# FINAL_schematic.net
KiCad netlist of a schematic drawn in EAGLE
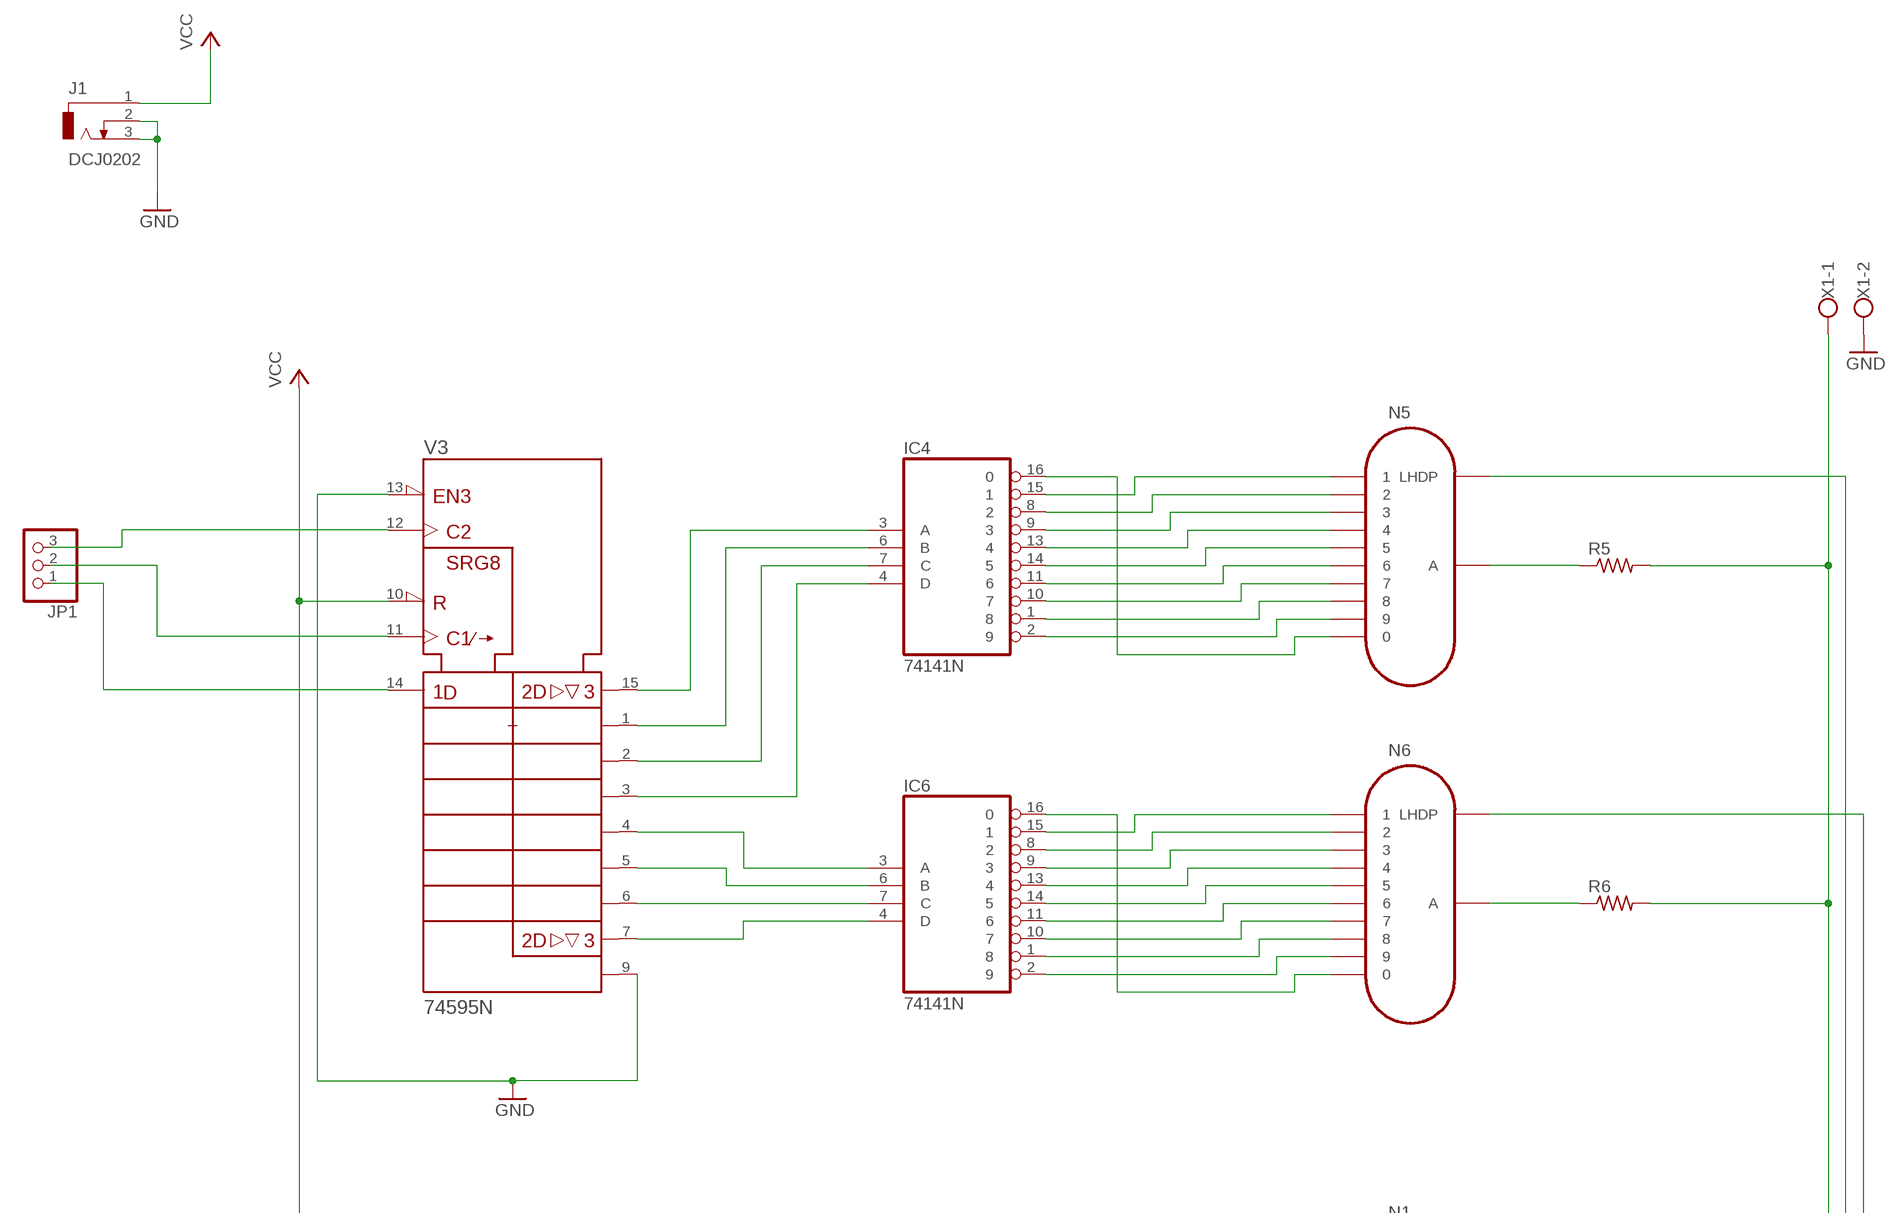
[diagram p0: schematic, sheet 1, part 1 of 2]
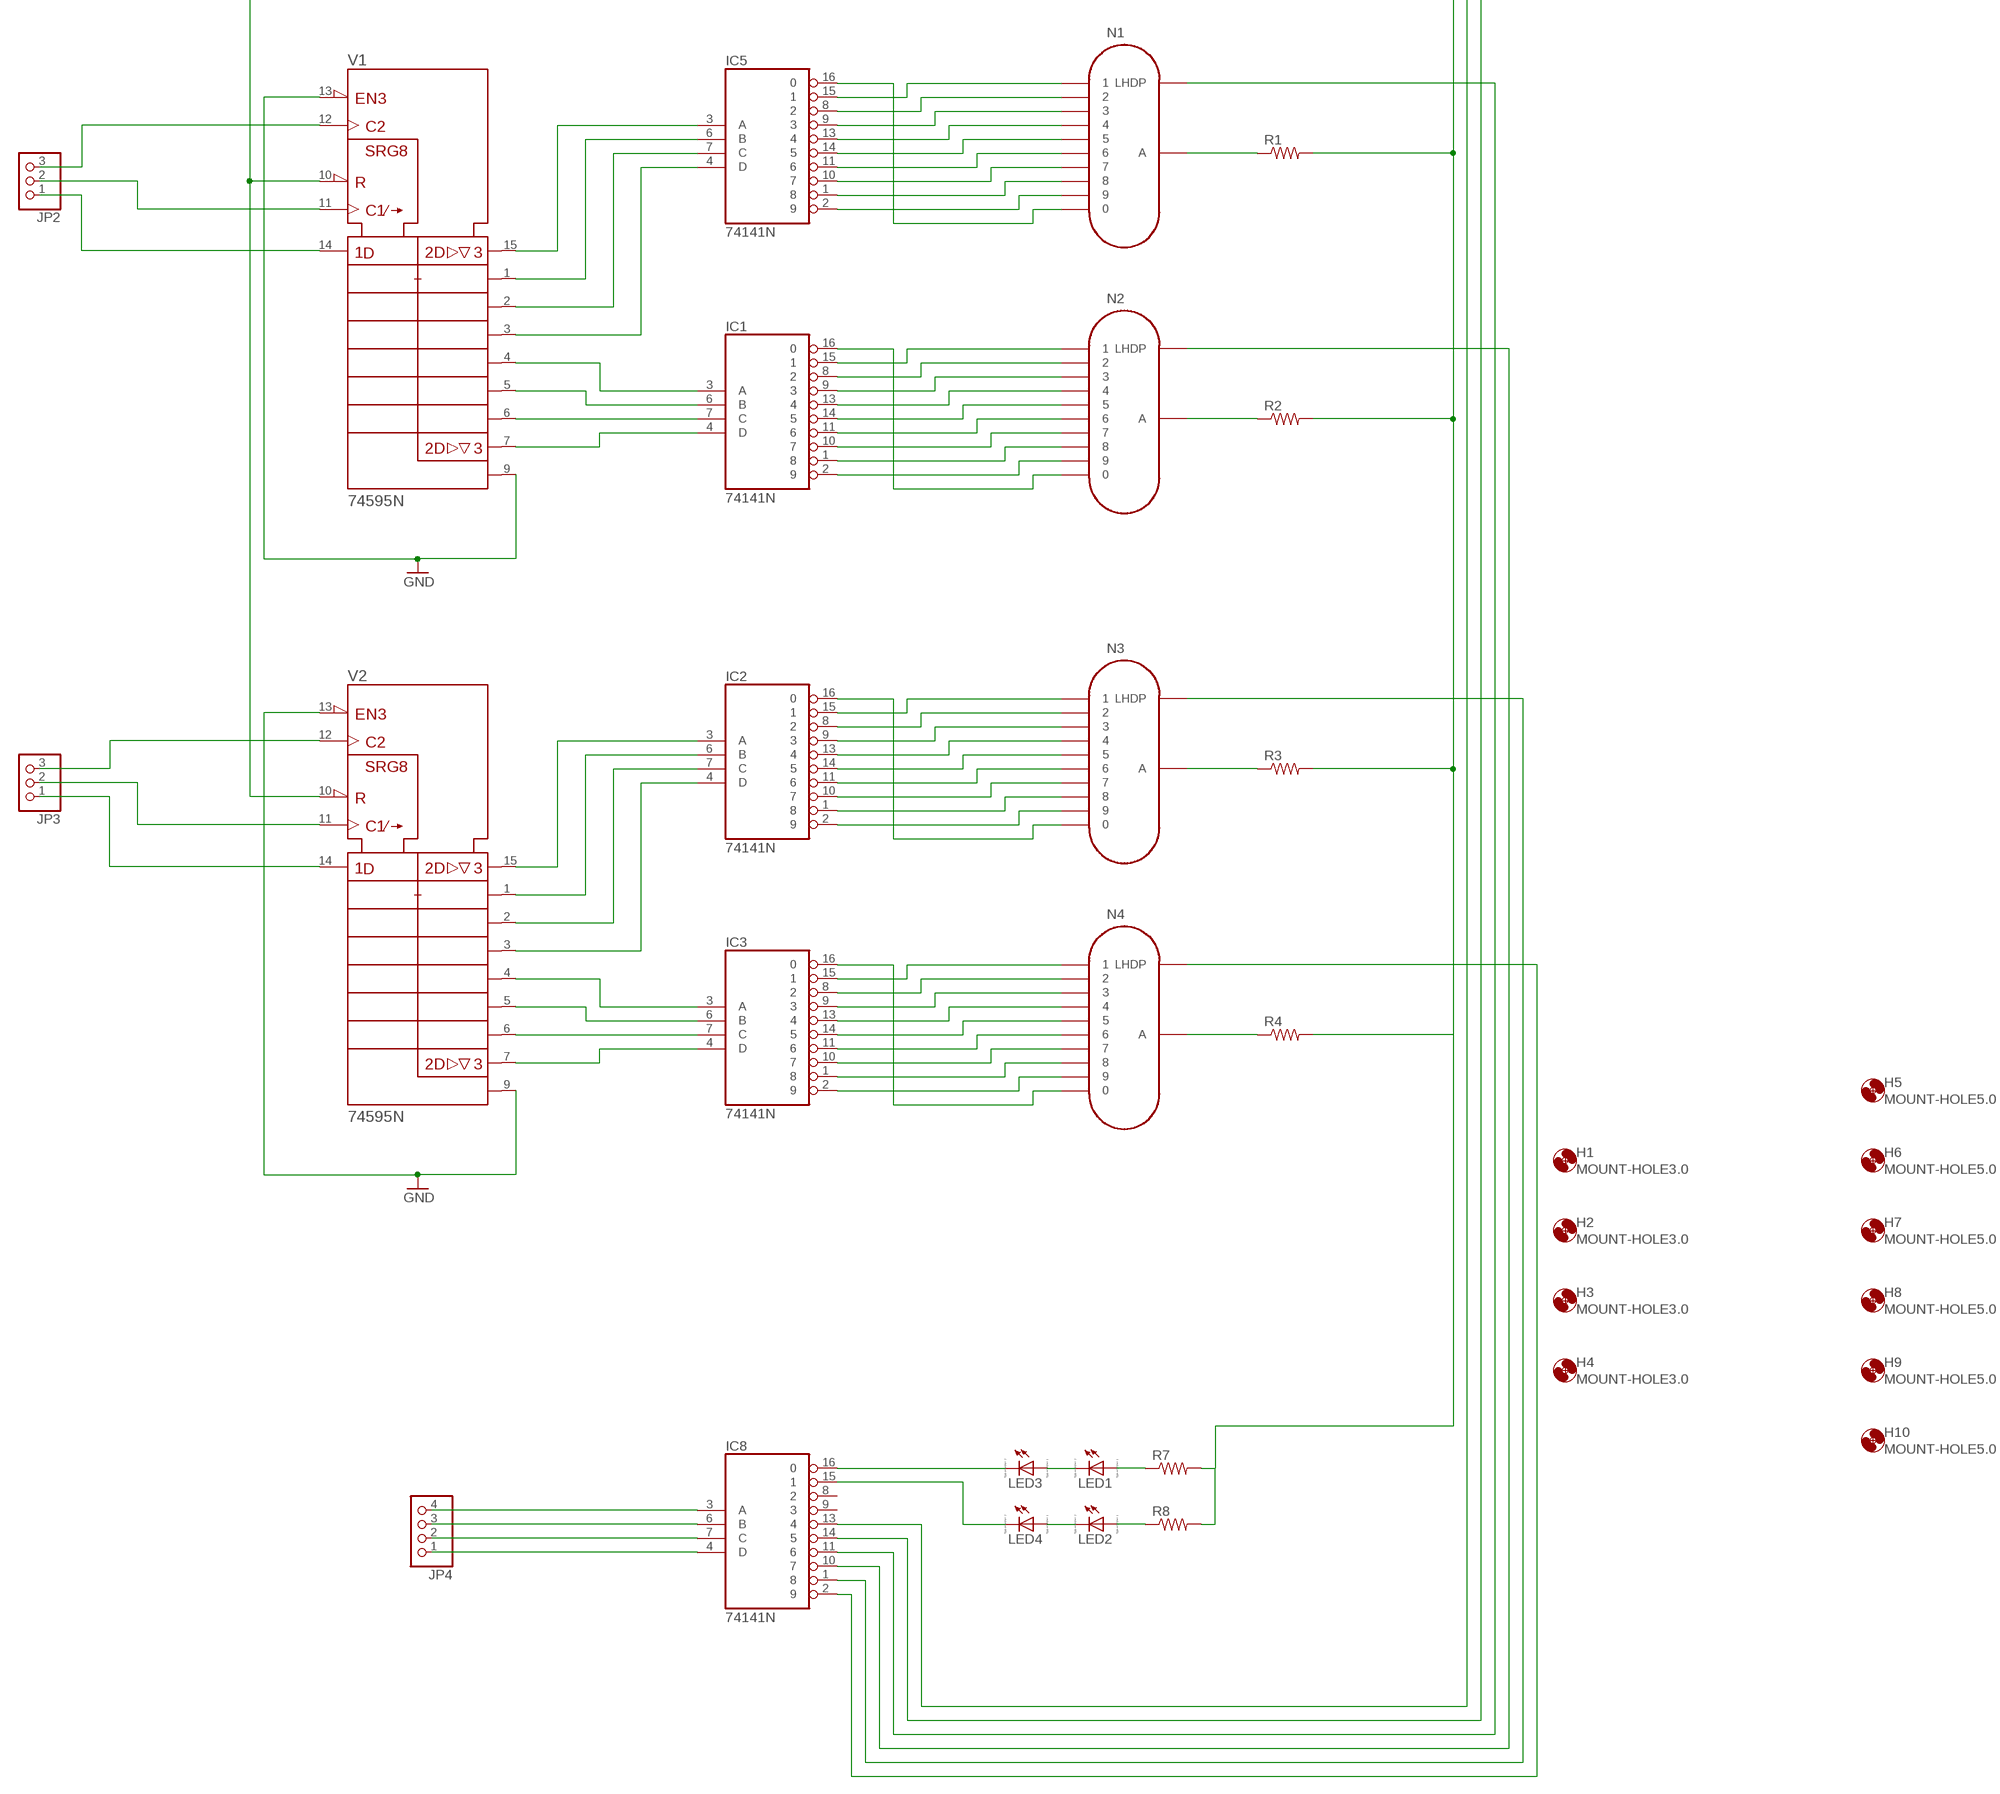
[diagram p1: schematic, sheet 1, part 2 of 2]

(export (version "E")
  (design (tool "Eeschema 10.0.6"))
  (components
    (comp (ref "H1")
      (value "MOUNT-HOLE3.0")
      (footprint "eagle-import:3,0")
      (libsource (lib "eagle-import") (part "MOUNT-HOLE3.0"))
    )
    (comp (ref "H2")
      (value "MOUNT-HOLE3.0")
      (footprint "eagle-import:3,0")
      (libsource (lib "eagle-import") (part "MOUNT-HOLE3.0"))
    )
    (comp (ref "H3")
      (value "MOUNT-HOLE3.0")
      (footprint "eagle-import:3,0")
      (libsource (lib "eagle-import") (part "MOUNT-HOLE3.0"))
    )
    (comp (ref "H4")
      (value "MOUNT-HOLE3.0")
      (footprint "eagle-import:3,0")
      (libsource (lib "eagle-import") (part "MOUNT-HOLE3.0"))
    )
    (comp (ref "H5")
      (value "MOUNT-HOLE5.0")
      (footprint "eagle-import:5,0")
      (libsource (lib "eagle-import") (part "MOUNT-HOLE5.0"))
    )
    (comp (ref "H6")
      (value "MOUNT-HOLE5.0")
      (footprint "eagle-import:5,0")
      (libsource (lib "eagle-import") (part "MOUNT-HOLE5.0"))
    )
    (comp (ref "H7")
      (value "MOUNT-HOLE5.0")
      (footprint "eagle-import:5,0")
      (libsource (lib "eagle-import") (part "MOUNT-HOLE5.0"))
    )
    (comp (ref "H8")
      (value "MOUNT-HOLE5.0")
      (footprint "eagle-import:5,0")
      (libsource (lib "eagle-import") (part "MOUNT-HOLE5.0"))
    )
    (comp (ref "H9")
      (value "MOUNT-HOLE5.0")
      (footprint "eagle-import:5,0")
      (libsource (lib "eagle-import") (part "MOUNT-HOLE5.0"))
    )
    (comp (ref "H10")
      (value "MOUNT-HOLE5.0")
      (footprint "eagle-import:5,0")
      (libsource (lib "eagle-import") (part "MOUNT-HOLE5.0"))
    )
    (comp (ref "IC1")
      (value "74141N")
      (footprint "eagle-import:DIL16")
      (libsource (lib "eagle-import") (part "74141N"))
    )
    (comp (ref "IC2")
      (value "74141N")
      (footprint "eagle-import:DIL16")
      (libsource (lib "eagle-import") (part "74141N"))
    )
    (comp (ref "IC3")
      (value "74141N")
      (footprint "eagle-import:DIL16")
      (libsource (lib "eagle-import") (part "74141N"))
    )
    (comp (ref "IC4")
      (value "74141N")
      (footprint "eagle-import:DIL16")
      (libsource (lib "eagle-import") (part "74141N"))
    )
    (comp (ref "IC5")
      (value "74141N")
      (footprint "eagle-import:DIL16")
      (libsource (lib "eagle-import") (part "74141N"))
    )
    (comp (ref "IC6")
      (value "74141N")
      (footprint "eagle-import:DIL16")
      (libsource (lib "eagle-import") (part "74141N"))
    )
    (comp (ref "IC8")
      (value "74141N")
      (footprint "eagle-import:DIL16")
      (libsource (lib "eagle-import") (part "74141N"))
    )
    (comp (ref "J1")
      (value "DCJ0202")
      (footprint "eagle-import:DCJ0202")
      (libsource (lib "eagle-import") (part "DCJ0202"))
    )
    (comp (ref "JP1")
      (value "PINHD-1X3")
      (footprint "eagle-import:1X03")
      (libsource (lib "eagle-import") (part "PINHD-1X3"))
    )
    (comp (ref "JP2")
      (value "PINHD-1X3")
      (footprint "eagle-import:1X03")
      (libsource (lib "eagle-import") (part "PINHD-1X3"))
    )
    (comp (ref "JP3")
      (value "PINHD-1X3")
      (footprint "eagle-import:1X03")
      (libsource (lib "eagle-import") (part "PINHD-1X3"))
    )
    (comp (ref "JP4")
      (value "PINHD-1X4")
      (footprint "eagle-import:1X04")
      (libsource (lib "eagle-import") (part "PINHD-1X4"))
    )
    (comp (ref "LED1")
      (value "LED_ELD260")
      (footprint "eagle-import:LED_LD260")
      (libsource (lib "eagle-import") (part "LED_ELD260"))
    )
    (comp (ref "LED2")
      (value "LED_ELD260")
      (footprint "eagle-import:LED_LD260")
      (libsource (lib "eagle-import") (part "LED_ELD260"))
    )
    (comp (ref "LED3")
      (value "LED_ELD260")
      (footprint "eagle-import:LED_LD260")
      (libsource (lib "eagle-import") (part "LED_ELD260"))
    )
    (comp (ref "LED4")
      (value "LED_ELD260")
      (footprint "eagle-import:LED_LD260")
      (libsource (lib "eagle-import") (part "LED_ELD260"))
    )
    (comp (ref "N1")
      (value "IN-12B")
      (footprint "eagle-import:IN-12")
      (libsource (lib "eagle-import") (part "IN-12B"))
    )
    (comp (ref "N2")
      (value "IN-12B")
      (footprint "eagle-import:IN-12")
      (libsource (lib "eagle-import") (part "IN-12B"))
    )
    (comp (ref "N3")
      (value "IN-12B")
      (footprint "eagle-import:IN-12")
      (libsource (lib "eagle-import") (part "IN-12B"))
    )
    (comp (ref "N4")
      (value "IN-12B")
      (footprint "eagle-import:IN-12")
      (libsource (lib "eagle-import") (part "IN-12B"))
    )
    (comp (ref "N5")
      (value "IN-12B")
      (footprint "eagle-import:IN-12")
      (libsource (lib "eagle-import") (part "IN-12B"))
    )
    (comp (ref "N6")
      (value "IN-12B")
      (footprint "eagle-import:IN-12")
      (libsource (lib "eagle-import") (part "IN-12B"))
    )
    (comp (ref "R1")
      (value "R-US_0207/10")
      (footprint "eagle-import:0207_10")
      (libsource (lib "eagle-import") (part "R-US_0207/10"))
    )
    (comp (ref "R2")
      (value "R-US_0207/10")
      (footprint "eagle-import:0207_10")
      (libsource (lib "eagle-import") (part "R-US_0207/10"))
    )
    (comp (ref "R3")
      (value "R-US_0207/10")
      (footprint "eagle-import:0207_10")
      (libsource (lib "eagle-import") (part "R-US_0207/10"))
    )
    (comp (ref "R4")
      (value "R-US_0207/10")
      (footprint "eagle-import:0207_10")
      (libsource (lib "eagle-import") (part "R-US_0207/10"))
    )
    (comp (ref "R5")
      (value "R-US_0207/10")
      (footprint "eagle-import:0207_10")
      (libsource (lib "eagle-import") (part "R-US_0207/10"))
    )
    (comp (ref "R6")
      (value "R-US_0207/10")
      (footprint "eagle-import:0207_10")
      (libsource (lib "eagle-import") (part "R-US_0207/10"))
    )
    (comp (ref "R7")
      (value "R-US_0207/10")
      (footprint "eagle-import:0207_10")
      (libsource (lib "eagle-import") (part "R-US_0207/10"))
    )
    (comp (ref "R8")
      (value "R-US_0207/10")
      (footprint "eagle-import:0207_10")
      (libsource (lib "eagle-import") (part "R-US_0207/10"))
    )
    (comp (ref "V1")
      (value "74595N")
      (footprint "eagle-import:DIL16")
      (libsource (lib "eagle-import") (part "74595N"))
    )
    (comp (ref "V2")
      (value "74595N")
      (footprint "eagle-import:DIL16")
      (libsource (lib "eagle-import") (part "74595N"))
    )
    (comp (ref "V3")
      (value "74595N")
      (footprint "eagle-import:DIL16")
      (libsource (lib "eagle-import") (part "74595N"))
    )
    (comp (ref "X1")
      (value "W237-102")
      (footprint "eagle-import:W237-102")
      (fields (field (name "MPN") "237-102"))
      (libsource (lib "eagle-import") (part "W237-102"))
    )
  )
  (nets
    (net (code "1") (name "GND") (class "Default")
      (node (ref "J1") (pin "2") (pinfunction "2_2") (pintype "passive"))
      (node (ref "J1") (pin "3") (pinfunction "3_3") (pintype "passive"))
      (node (ref "V1") (pin "13") (pinfunction "~{G}_13") (pintype "input"))
      (node (ref "V1") (pin "9") (pinfunction "QH*_9") (pintype "output"))
      (node (ref "V2") (pin "13") (pinfunction "~{G}_13") (pintype "input"))
      (node (ref "V2") (pin "9") (pinfunction "QH*_9") (pintype "output"))
      (node (ref "V3") (pin "13") (pinfunction "~{G}_13") (pintype "input"))
      (node (ref "V3") (pin "9") (pinfunction "QH*_9") (pintype "output"))
      (node (ref "X1") (pin "2") (pinfunction "KL_2") (pintype "passive"))
    )
    (net (code "2") (name "Net-(IC1A-0)") (class "Default")
      (node (ref "IC1") (pin "16") (pinfunction "0_16") (pintype "open_collector"))
      (node (ref "N2") (pin "0") (pinfunction "0_0") (pintype "bidirectional"))
    )
    (net (code "3") (name "Net-(IC1A-1)") (class "Default")
      (node (ref "IC1") (pin "15") (pinfunction "1_15") (pintype "open_collector"))
      (node (ref "N2") (pin "1") (pinfunction "1_1") (pintype "bidirectional"))
    )
    (net (code "4") (name "Net-(IC1A-2)") (class "Default")
      (node (ref "IC1") (pin "8") (pinfunction "2_8") (pintype "open_collector"))
      (node (ref "N2") (pin "2") (pinfunction "2_2") (pintype "bidirectional"))
    )
    (net (code "5") (name "Net-(IC1A-3)") (class "Default")
      (node (ref "IC1") (pin "9") (pinfunction "3_9") (pintype "open_collector"))
      (node (ref "N2") (pin "3") (pinfunction "3_3") (pintype "bidirectional"))
    )
    (net (code "6") (name "Net-(IC1A-4)") (class "Default")
      (node (ref "IC1") (pin "13") (pinfunction "4_13") (pintype "open_collector"))
      (node (ref "N2") (pin "4") (pinfunction "4_4") (pintype "bidirectional"))
    )
    (net (code "7") (name "Net-(IC1A-5)") (class "Default")
      (node (ref "IC1") (pin "14") (pinfunction "5_14") (pintype "open_collector"))
      (node (ref "N2") (pin "5") (pinfunction "5_5") (pintype "bidirectional"))
    )
    (net (code "8") (name "Net-(IC1A-6)") (class "Default")
      (node (ref "IC1") (pin "11") (pinfunction "6_11") (pintype "open_collector"))
      (node (ref "N2") (pin "6") (pinfunction "6_6") (pintype "bidirectional"))
    )
    (net (code "9") (name "Net-(IC1A-7)") (class "Default")
      (node (ref "IC1") (pin "10") (pinfunction "7_10") (pintype "open_collector"))
      (node (ref "N2") (pin "7") (pinfunction "7_7") (pintype "bidirectional"))
    )
    (net (code "10") (name "Net-(IC1A-8)") (class "Default")
      (node (ref "IC1") (pin "1") (pinfunction "8_1") (pintype "open_collector"))
      (node (ref "N2") (pin "8") (pinfunction "8_8") (pintype "bidirectional"))
    )
    (net (code "11") (name "Net-(IC1A-9)") (class "Default")
      (node (ref "IC1") (pin "2") (pinfunction "9_2") (pintype "open_collector"))
      (node (ref "N2") (pin "9") (pinfunction "9_9") (pintype "bidirectional"))
    )
    (net (code "12") (name "Net-(IC1A-A)") (class "Default")
      (node (ref "IC1") (pin "3") (pinfunction "A_3") (pintype "input"))
      (node (ref "V1") (pin "4") (pinfunction "QE_4") (pintype "tri_state"))
    )
    (net (code "13") (name "Net-(IC1A-B)") (class "Default")
      (node (ref "IC1") (pin "6") (pinfunction "B_6") (pintype "input"))
      (node (ref "V1") (pin "5") (pinfunction "QF_5") (pintype "tri_state"))
    )
    (net (code "14") (name "Net-(IC1A-C)") (class "Default")
      (node (ref "IC1") (pin "7") (pinfunction "C_7") (pintype "input"))
      (node (ref "V1") (pin "6") (pinfunction "QG_6") (pintype "tri_state"))
    )
    (net (code "15") (name "Net-(IC1A-D)") (class "Default")
      (node (ref "IC1") (pin "4") (pinfunction "D_4") (pintype "input"))
      (node (ref "V1") (pin "7") (pinfunction "QH_7") (pintype "tri_state"))
    )
    (net (code "16") (name "Net-(IC2A-0)") (class "Default")
      (node (ref "IC2") (pin "16") (pinfunction "0_16") (pintype "open_collector"))
      (node (ref "N3") (pin "0") (pinfunction "0_0") (pintype "bidirectional"))
    )
    (net (code "17") (name "Net-(IC2A-1)") (class "Default")
      (node (ref "IC2") (pin "15") (pinfunction "1_15") (pintype "open_collector"))
      (node (ref "N3") (pin "1") (pinfunction "1_1") (pintype "bidirectional"))
    )
    (net (code "18") (name "Net-(IC2A-2)") (class "Default")
      (node (ref "IC2") (pin "8") (pinfunction "2_8") (pintype "open_collector"))
      (node (ref "N3") (pin "2") (pinfunction "2_2") (pintype "bidirectional"))
    )
    (net (code "19") (name "Net-(IC2A-3)") (class "Default")
      (node (ref "IC2") (pin "9") (pinfunction "3_9") (pintype "open_collector"))
      (node (ref "N3") (pin "3") (pinfunction "3_3") (pintype "bidirectional"))
    )
    (net (code "20") (name "Net-(IC2A-4)") (class "Default")
      (node (ref "IC2") (pin "13") (pinfunction "4_13") (pintype "open_collector"))
      (node (ref "N3") (pin "4") (pinfunction "4_4") (pintype "bidirectional"))
    )
    (net (code "21") (name "Net-(IC2A-5)") (class "Default")
      (node (ref "IC2") (pin "14") (pinfunction "5_14") (pintype "open_collector"))
      (node (ref "N3") (pin "5") (pinfunction "5_5") (pintype "bidirectional"))
    )
    (net (code "22") (name "Net-(IC2A-6)") (class "Default")
      (node (ref "IC2") (pin "11") (pinfunction "6_11") (pintype "open_collector"))
      (node (ref "N3") (pin "6") (pinfunction "6_6") (pintype "bidirectional"))
    )
    (net (code "23") (name "Net-(IC2A-7)") (class "Default")
      (node (ref "IC2") (pin "10") (pinfunction "7_10") (pintype "open_collector"))
      (node (ref "N3") (pin "7") (pinfunction "7_7") (pintype "bidirectional"))
    )
    (net (code "24") (name "Net-(IC2A-8)") (class "Default")
      (node (ref "IC2") (pin "1") (pinfunction "8_1") (pintype "open_collector"))
      (node (ref "N3") (pin "8") (pinfunction "8_8") (pintype "bidirectional"))
    )
    (net (code "25") (name "Net-(IC2A-9)") (class "Default")
      (node (ref "IC2") (pin "2") (pinfunction "9_2") (pintype "open_collector"))
      (node (ref "N3") (pin "9") (pinfunction "9_9") (pintype "bidirectional"))
    )
    (net (code "26") (name "Net-(IC2A-A)") (class "Default")
      (node (ref "IC2") (pin "3") (pinfunction "A_3") (pintype "input"))
      (node (ref "V2") (pin "15") (pinfunction "QA_15") (pintype "tri_state"))
    )
    (net (code "27") (name "Net-(IC2A-B)") (class "Default")
      (node (ref "IC2") (pin "6") (pinfunction "B_6") (pintype "input"))
      (node (ref "V2") (pin "1") (pinfunction "QB_1") (pintype "tri_state"))
    )
    (net (code "28") (name "Net-(IC2A-C)") (class "Default")
      (node (ref "IC2") (pin "7") (pinfunction "C_7") (pintype "input"))
      (node (ref "V2") (pin "2") (pinfunction "QC_2") (pintype "tri_state"))
    )
    (net (code "29") (name "Net-(IC2A-D)") (class "Default")
      (node (ref "IC2") (pin "4") (pinfunction "D_4") (pintype "input"))
      (node (ref "V2") (pin "3") (pinfunction "QD_3") (pintype "tri_state"))
    )
    (net (code "30") (name "Net-(IC3A-0)") (class "Default")
      (node (ref "IC3") (pin "16") (pinfunction "0_16") (pintype "open_collector"))
      (node (ref "N4") (pin "0") (pinfunction "0_0") (pintype "bidirectional"))
    )
    (net (code "31") (name "Net-(IC3A-1)") (class "Default")
      (node (ref "IC3") (pin "15") (pinfunction "1_15") (pintype "open_collector"))
      (node (ref "N4") (pin "1") (pinfunction "1_1") (pintype "bidirectional"))
    )
    (net (code "32") (name "Net-(IC3A-2)") (class "Default")
      (node (ref "IC3") (pin "8") (pinfunction "2_8") (pintype "open_collector"))
      (node (ref "N4") (pin "2") (pinfunction "2_2") (pintype "bidirectional"))
    )
    (net (code "33") (name "Net-(IC3A-3)") (class "Default")
      (node (ref "IC3") (pin "9") (pinfunction "3_9") (pintype "open_collector"))
      (node (ref "N4") (pin "3") (pinfunction "3_3") (pintype "bidirectional"))
    )
    (net (code "34") (name "Net-(IC3A-4)") (class "Default")
      (node (ref "IC3") (pin "13") (pinfunction "4_13") (pintype "open_collector"))
      (node (ref "N4") (pin "4") (pinfunction "4_4") (pintype "bidirectional"))
    )
    (net (code "35") (name "Net-(IC3A-5)") (class "Default")
      (node (ref "IC3") (pin "14") (pinfunction "5_14") (pintype "open_collector"))
      (node (ref "N4") (pin "5") (pinfunction "5_5") (pintype "bidirectional"))
    )
    (net (code "36") (name "Net-(IC3A-6)") (class "Default")
      (node (ref "IC3") (pin "11") (pinfunction "6_11") (pintype "open_collector"))
      (node (ref "N4") (pin "6") (pinfunction "6_6") (pintype "bidirectional"))
    )
    (net (code "37") (name "Net-(IC3A-7)") (class "Default")
      (node (ref "IC3") (pin "10") (pinfunction "7_10") (pintype "open_collector"))
      (node (ref "N4") (pin "7") (pinfunction "7_7") (pintype "bidirectional"))
    )
    (net (code "38") (name "Net-(IC3A-8)") (class "Default")
      (node (ref "IC3") (pin "1") (pinfunction "8_1") (pintype "open_collector"))
      (node (ref "N4") (pin "8") (pinfunction "8_8") (pintype "bidirectional"))
    )
    (net (code "39") (name "Net-(IC3A-9)") (class "Default")
      (node (ref "IC3") (pin "2") (pinfunction "9_2") (pintype "open_collector"))
      (node (ref "N4") (pin "9") (pinfunction "9_9") (pintype "bidirectional"))
    )
    (net (code "40") (name "Net-(IC3A-A)") (class "Default")
      (node (ref "IC3") (pin "3") (pinfunction "A_3") (pintype "input"))
      (node (ref "V2") (pin "4") (pinfunction "QE_4") (pintype "tri_state"))
    )
    (net (code "41") (name "Net-(IC3A-B)") (class "Default")
      (node (ref "IC3") (pin "6") (pinfunction "B_6") (pintype "input"))
      (node (ref "V2") (pin "5") (pinfunction "QF_5") (pintype "tri_state"))
    )
    (net (code "42") (name "Net-(IC3A-C)") (class "Default")
      (node (ref "IC3") (pin "7") (pinfunction "C_7") (pintype "input"))
      (node (ref "V2") (pin "6") (pinfunction "QG_6") (pintype "tri_state"))
    )
    (net (code "43") (name "Net-(IC3A-D)") (class "Default")
      (node (ref "IC3") (pin "4") (pinfunction "D_4") (pintype "input"))
      (node (ref "V2") (pin "7") (pinfunction "QH_7") (pintype "tri_state"))
    )
    (net (code "44") (name "Net-(IC4A-0)") (class "Default")
      (node (ref "IC4") (pin "16") (pinfunction "0_16") (pintype "open_collector"))
      (node (ref "N5") (pin "0") (pinfunction "0_0") (pintype "bidirectional"))
    )
    (net (code "45") (name "Net-(IC4A-1)") (class "Default")
      (node (ref "IC4") (pin "15") (pinfunction "1_15") (pintype "open_collector"))
      (node (ref "N5") (pin "1") (pinfunction "1_1") (pintype "bidirectional"))
    )
    (net (code "46") (name "Net-(IC4A-2)") (class "Default")
      (node (ref "IC4") (pin "8") (pinfunction "2_8") (pintype "open_collector"))
      (node (ref "N5") (pin "2") (pinfunction "2_2") (pintype "bidirectional"))
    )
    (net (code "47") (name "Net-(IC4A-3)") (class "Default")
      (node (ref "IC4") (pin "9") (pinfunction "3_9") (pintype "open_collector"))
      (node (ref "N5") (pin "3") (pinfunction "3_3") (pintype "bidirectional"))
    )
    (net (code "48") (name "Net-(IC4A-4)") (class "Default")
      (node (ref "IC4") (pin "13") (pinfunction "4_13") (pintype "open_collector"))
      (node (ref "N5") (pin "4") (pinfunction "4_4") (pintype "bidirectional"))
    )
    (net (code "49") (name "Net-(IC4A-5)") (class "Default")
      (node (ref "IC4") (pin "14") (pinfunction "5_14") (pintype "open_collector"))
      (node (ref "N5") (pin "5") (pinfunction "5_5") (pintype "bidirectional"))
    )
    (net (code "50") (name "Net-(IC4A-6)") (class "Default")
      (node (ref "IC4") (pin "11") (pinfunction "6_11") (pintype "open_collector"))
      (node (ref "N5") (pin "6") (pinfunction "6_6") (pintype "bidirectional"))
    )
    (net (code "51") (name "Net-(IC4A-7)") (class "Default")
      (node (ref "IC4") (pin "10") (pinfunction "7_10") (pintype "open_collector"))
      (node (ref "N5") (pin "7") (pinfunction "7_7") (pintype "bidirectional"))
    )
    (net (code "52") (name "Net-(IC4A-8)") (class "Default")
      (node (ref "IC4") (pin "1") (pinfunction "8_1") (pintype "open_collector"))
      (node (ref "N5") (pin "8") (pinfunction "8_8") (pintype "bidirectional"))
    )
    (net (code "53") (name "Net-(IC4A-9)") (class "Default")
      (node (ref "IC4") (pin "2") (pinfunction "9_2") (pintype "open_collector"))
      (node (ref "N5") (pin "9") (pinfunction "9_9") (pintype "bidirectional"))
    )
    (net (code "54") (name "Net-(IC4A-A)") (class "Default")
      (node (ref "IC4") (pin "3") (pinfunction "A_3") (pintype "input"))
      (node (ref "V3") (pin "15") (pinfunction "QA_15") (pintype "tri_state"))
    )
    (net (code "55") (name "Net-(IC4A-B)") (class "Default")
      (node (ref "IC4") (pin "6") (pinfunction "B_6") (pintype "input"))
      (node (ref "V3") (pin "1") (pinfunction "QB_1") (pintype "tri_state"))
    )
    (net (code "56") (name "Net-(IC4A-C)") (class "Default")
      (node (ref "IC4") (pin "7") (pinfunction "C_7") (pintype "input"))
      (node (ref "V3") (pin "2") (pinfunction "QC_2") (pintype "tri_state"))
    )
    (net (code "57") (name "Net-(IC4A-D)") (class "Default")
      (node (ref "IC4") (pin "4") (pinfunction "D_4") (pintype "input"))
      (node (ref "V3") (pin "3") (pinfunction "QD_3") (pintype "tri_state"))
    )
    (net (code "58") (name "Net-(IC5A-0)") (class "Default")
      (node (ref "IC5") (pin "16") (pinfunction "0_16") (pintype "open_collector"))
      (node (ref "N1") (pin "0") (pinfunction "0_0") (pintype "bidirectional"))
    )
    (net (code "59") (name "Net-(IC5A-1)") (class "Default")
      (node (ref "IC5") (pin "15") (pinfunction "1_15") (pintype "open_collector"))
      (node (ref "N1") (pin "1") (pinfunction "1_1") (pintype "bidirectional"))
    )
    (net (code "60") (name "Net-(IC5A-2)") (class "Default")
      (node (ref "IC5") (pin "8") (pinfunction "2_8") (pintype "open_collector"))
      (node (ref "N1") (pin "2") (pinfunction "2_2") (pintype "bidirectional"))
    )
    (net (code "61") (name "Net-(IC5A-3)") (class "Default")
      (node (ref "IC5") (pin "9") (pinfunction "3_9") (pintype "open_collector"))
      (node (ref "N1") (pin "3") (pinfunction "3_3") (pintype "bidirectional"))
    )
    (net (code "62") (name "Net-(IC5A-4)") (class "Default")
      (node (ref "IC5") (pin "13") (pinfunction "4_13") (pintype "open_collector"))
      (node (ref "N1") (pin "4") (pinfunction "4_4") (pintype "bidirectional"))
    )
    (net (code "63") (name "Net-(IC5A-5)") (class "Default")
      (node (ref "IC5") (pin "14") (pinfunction "5_14") (pintype "open_collector"))
      (node (ref "N1") (pin "5") (pinfunction "5_5") (pintype "bidirectional"))
    )
    (net (code "64") (name "Net-(IC5A-6)") (class "Default")
      (node (ref "IC5") (pin "11") (pinfunction "6_11") (pintype "open_collector"))
      (node (ref "N1") (pin "6") (pinfunction "6_6") (pintype "bidirectional"))
    )
    (net (code "65") (name "Net-(IC5A-7)") (class "Default")
      (node (ref "IC5") (pin "10") (pinfunction "7_10") (pintype "open_collector"))
      (node (ref "N1") (pin "7") (pinfunction "7_7") (pintype "bidirectional"))
    )
    (net (code "66") (name "Net-(IC5A-8)") (class "Default")
      (node (ref "IC5") (pin "1") (pinfunction "8_1") (pintype "open_collector"))
      (node (ref "N1") (pin "8") (pinfunction "8_8") (pintype "bidirectional"))
    )
    (net (code "67") (name "Net-(IC5A-9)") (class "Default")
      (node (ref "IC5") (pin "2") (pinfunction "9_2") (pintype "open_collector"))
      (node (ref "N1") (pin "9") (pinfunction "9_9") (pintype "bidirectional"))
    )
    (net (code "68") (name "Net-(IC5A-A)") (class "Default")
      (node (ref "IC5") (pin "3") (pinfunction "A_3") (pintype "input"))
      (node (ref "V1") (pin "15") (pinfunction "QA_15") (pintype "tri_state"))
    )
    (net (code "69") (name "Net-(IC5A-B)") (class "Default")
      (node (ref "IC5") (pin "6") (pinfunction "B_6") (pintype "input"))
      (node (ref "V1") (pin "1") (pinfunction "QB_1") (pintype "tri_state"))
    )
    (net (code "70") (name "Net-(IC5A-C)") (class "Default")
      (node (ref "IC5") (pin "7") (pinfunction "C_7") (pintype "input"))
      (node (ref "V1") (pin "2") (pinfunction "QC_2") (pintype "tri_state"))
    )
    (net (code "71") (name "Net-(IC5A-D)") (class "Default")
      (node (ref "IC5") (pin "4") (pinfunction "D_4") (pintype "input"))
      (node (ref "V1") (pin "3") (pinfunction "QD_3") (pintype "tri_state"))
    )
    (net (code "72") (name "Net-(IC6A-0)") (class "Default")
      (node (ref "IC6") (pin "16") (pinfunction "0_16") (pintype "open_collector"))
      (node (ref "N6") (pin "0") (pinfunction "0_0") (pintype "bidirectional"))
    )
    (net (code "73") (name "Net-(IC6A-1)") (class "Default")
      (node (ref "IC6") (pin "15") (pinfunction "1_15") (pintype "open_collector"))
      (node (ref "N6") (pin "1") (pinfunction "1_1") (pintype "bidirectional"))
    )
    (net (code "74") (name "Net-(IC6A-2)") (class "Default")
      (node (ref "IC6") (pin "8") (pinfunction "2_8") (pintype "open_collector"))
      (node (ref "N6") (pin "2") (pinfunction "2_2") (pintype "bidirectional"))
    )
    (net (code "75") (name "Net-(IC6A-3)") (class "Default")
      (node (ref "IC6") (pin "9") (pinfunction "3_9") (pintype "open_collector"))
      (node (ref "N6") (pin "3") (pinfunction "3_3") (pintype "bidirectional"))
    )
    (net (code "76") (name "Net-(IC6A-4)") (class "Default")
      (node (ref "IC6") (pin "13") (pinfunction "4_13") (pintype "open_collector"))
      (node (ref "N6") (pin "4") (pinfunction "4_4") (pintype "bidirectional"))
    )
    (net (code "77") (name "Net-(IC6A-5)") (class "Default")
      (node (ref "IC6") (pin "14") (pinfunction "5_14") (pintype "open_collector"))
      (node (ref "N6") (pin "5") (pinfunction "5_5") (pintype "bidirectional"))
    )
    (net (code "78") (name "Net-(IC6A-6)") (class "Default")
      (node (ref "IC6") (pin "11") (pinfunction "6_11") (pintype "open_collector"))
      (node (ref "N6") (pin "6") (pinfunction "6_6") (pintype "bidirectional"))
    )
    (net (code "79") (name "Net-(IC6A-7)") (class "Default")
      (node (ref "IC6") (pin "10") (pinfunction "7_10") (pintype "open_collector"))
      (node (ref "N6") (pin "7") (pinfunction "7_7") (pintype "bidirectional"))
    )
    (net (code "80") (name "Net-(IC6A-8)") (class "Default")
      (node (ref "IC6") (pin "1") (pinfunction "8_1") (pintype "open_collector"))
      (node (ref "N6") (pin "8") (pinfunction "8_8") (pintype "bidirectional"))
    )
    (net (code "81") (name "Net-(IC6A-9)") (class "Default")
      (node (ref "IC6") (pin "2") (pinfunction "9_2") (pintype "open_collector"))
      (node (ref "N6") (pin "9") (pinfunction "9_9") (pintype "bidirectional"))
    )
    (net (code "82") (name "Net-(IC6A-A)") (class "Default")
      (node (ref "IC6") (pin "3") (pinfunction "A_3") (pintype "input"))
      (node (ref "V3") (pin "4") (pinfunction "QE_4") (pintype "tri_state"))
    )
    (net (code "83") (name "Net-(IC6A-B)") (class "Default")
      (node (ref "IC6") (pin "6") (pinfunction "B_6") (pintype "input"))
      (node (ref "V3") (pin "5") (pinfunction "QF_5") (pintype "tri_state"))
    )
    (net (code "84") (name "Net-(IC6A-C)") (class "Default")
      (node (ref "IC6") (pin "7") (pinfunction "C_7") (pintype "input"))
      (node (ref "V3") (pin "6") (pinfunction "QG_6") (pintype "tri_state"))
    )
    (net (code "85") (name "Net-(IC6A-D)") (class "Default")
      (node (ref "IC6") (pin "4") (pinfunction "D_4") (pintype "input"))
      (node (ref "V3") (pin "7") (pinfunction "QH_7") (pintype "tri_state"))
    )
    (net (code "86") (name "Net-(IC8A-0)") (class "Default")
      (node (ref "IC8") (pin "16") (pinfunction "0_16") (pintype "open_collector"))
      (node (ref "LED3") (pin "K") (pinfunction "C_K") (pintype "passive"))
    )
    (net (code "87") (name "Net-(IC8A-1)") (class "Default")
      (node (ref "IC8") (pin "15") (pinfunction "1_15") (pintype "open_collector"))
      (node (ref "LED4") (pin "K") (pinfunction "C_K") (pintype "passive"))
    )
    (net (code "88") (name "Net-(IC8A-4)") (class "Default")
      (node (ref "IC8") (pin "13") (pinfunction "4_13") (pintype "open_collector"))
      (node (ref "N5") (pin "LHDP") (pinfunction "LHDP_LHDP") (pintype "bidirectional"))
    )
    (net (code "89") (name "Net-(IC8A-5)") (class "Default")
      (node (ref "IC8") (pin "14") (pinfunction "5_14") (pintype "open_collector"))
      (node (ref "N6") (pin "LHDP") (pinfunction "LHDP_LHDP") (pintype "bidirectional"))
    )
    (net (code "90") (name "Net-(IC8A-6)") (class "Default")
      (node (ref "IC8") (pin "11") (pinfunction "6_11") (pintype "open_collector"))
      (node (ref "N1") (pin "LHDP") (pinfunction "LHDP_LHDP") (pintype "bidirectional"))
    )
    (net (code "91") (name "Net-(IC8A-7)") (class "Default")
      (node (ref "IC8") (pin "10") (pinfunction "7_10") (pintype "open_collector"))
      (node (ref "N2") (pin "LHDP") (pinfunction "LHDP_LHDP") (pintype "bidirectional"))
    )
    (net (code "92") (name "Net-(IC8A-8)") (class "Default")
      (node (ref "IC8") (pin "1") (pinfunction "8_1") (pintype "open_collector"))
      (node (ref "N3") (pin "LHDP") (pinfunction "LHDP_LHDP") (pintype "bidirectional"))
    )
    (net (code "93") (name "Net-(IC8A-9)") (class "Default")
      (node (ref "IC8") (pin "2") (pinfunction "9_2") (pintype "open_collector"))
      (node (ref "N4") (pin "LHDP") (pinfunction "LHDP_LHDP") (pintype "bidirectional"))
    )
    (net (code "94") (name "Net-(IC8A-A)") (class "Default")
      (node (ref "IC8") (pin "3") (pinfunction "A_3") (pintype "input"))
      (node (ref "JP4") (pin "4") (pinfunction "4_4") (pintype "passive"))
    )
    (net (code "95") (name "Net-(IC8A-B)") (class "Default")
      (node (ref "IC8") (pin "6") (pinfunction "B_6") (pintype "input"))
      (node (ref "JP4") (pin "3") (pinfunction "3_3") (pintype "passive"))
    )
    (net (code "96") (name "Net-(IC8A-C)") (class "Default")
      (node (ref "IC8") (pin "7") (pinfunction "C_7") (pintype "input"))
      (node (ref "JP4") (pin "2") (pinfunction "2_2") (pintype "passive"))
    )
    (net (code "97") (name "Net-(IC8A-D)") (class "Default")
      (node (ref "IC8") (pin "4") (pinfunction "D_4") (pintype "input"))
      (node (ref "JP4") (pin "1") (pinfunction "1_1") (pintype "passive"))
    )
    (net (code "98") (name "Net-(LED1-C)") (class "Default")
      (node (ref "LED1") (pin "K") (pinfunction "C_K") (pintype "passive"))
      (node (ref "LED3") (pin "A") (pinfunction "A_A") (pintype "passive"))
    )
    (net (code "99") (name "Net-(LED1-PadA)") (class "Default")
      (node (ref "LED1") (pin "A") (pinfunction "A_A") (pintype "passive"))
      (node (ref "R7") (pin "1") (pinfunction "1_1") (pintype "passive"))
    )
    (net (code "100") (name "Net-(LED2-C)") (class "Default")
      (node (ref "LED2") (pin "K") (pinfunction "C_K") (pintype "passive"))
      (node (ref "LED4") (pin "A") (pinfunction "A_A") (pintype "passive"))
    )
    (net (code "101") (name "Net-(LED2-PadA)") (class "Default")
      (node (ref "LED2") (pin "A") (pinfunction "A_A") (pintype "passive"))
      (node (ref "R8") (pin "1") (pinfunction "1_1") (pintype "passive"))
    )
    (net (code "102") (name "Net-(N1-PadA)") (class "Default")
      (node (ref "N1") (pin "A") (pinfunction "A_A") (pintype "bidirectional"))
      (node (ref "R1") (pin "1") (pinfunction "1_1") (pintype "passive"))
    )
    (net (code "103") (name "Net-(N2-PadA)") (class "Default")
      (node (ref "N2") (pin "A") (pinfunction "A_A") (pintype "bidirectional"))
      (node (ref "R2") (pin "1") (pinfunction "1_1") (pintype "passive"))
    )
    (net (code "104") (name "Net-(N3-PadA)") (class "Default")
      (node (ref "N3") (pin "A") (pinfunction "A_A") (pintype "bidirectional"))
      (node (ref "R3") (pin "1") (pinfunction "1_1") (pintype "passive"))
    )
    (net (code "105") (name "Net-(N4-PadA)") (class "Default")
      (node (ref "N4") (pin "A") (pinfunction "A_A") (pintype "bidirectional"))
      (node (ref "R4") (pin "1") (pinfunction "1_1") (pintype "passive"))
    )
    (net (code "106") (name "Net-(N5-PadA)") (class "Default")
      (node (ref "N5") (pin "A") (pinfunction "A_A") (pintype "bidirectional"))
      (node (ref "R5") (pin "1") (pinfunction "1_1") (pintype "passive"))
    )
    (net (code "107") (name "Net-(N6-PadA)") (class "Default")
      (node (ref "N6") (pin "A") (pinfunction "A_A") (pintype "bidirectional"))
      (node (ref "R6") (pin "1") (pinfunction "1_1") (pintype "passive"))
    )
    (net (code "108") (name "Net-(V1C-RCK)") (class "Default")
      (node (ref "JP2") (pin "3") (pinfunction "3_3") (pintype "passive"))
      (node (ref "V1") (pin "12") (pinfunction "RCK_12") (pintype "input"))
    )
    (net (code "109") (name "Net-(V1C-SER)") (class "Default")
      (node (ref "JP2") (pin "1") (pinfunction "1_1") (pintype "passive"))
      (node (ref "V1") (pin "14") (pinfunction "SER_14") (pintype "input"))
    )
    (net (code "110") (name "Net-(V1C-SRCK)") (class "Default")
      (node (ref "JP2") (pin "2") (pinfunction "2_2") (pintype "passive"))
      (node (ref "V1") (pin "11") (pinfunction "SRCK_11") (pintype "input"))
    )
    (net (code "111") (name "Net-(V2C-RCK)") (class "Default")
      (node (ref "JP3") (pin "3") (pinfunction "3_3") (pintype "passive"))
      (node (ref "V2") (pin "12") (pinfunction "RCK_12") (pintype "input"))
    )
    (net (code "112") (name "Net-(V2C-SER)") (class "Default")
      (node (ref "JP3") (pin "1") (pinfunction "1_1") (pintype "passive"))
      (node (ref "V2") (pin "14") (pinfunction "SER_14") (pintype "input"))
    )
    (net (code "113") (name "Net-(V2C-SRCK)") (class "Default")
      (node (ref "JP3") (pin "2") (pinfunction "2_2") (pintype "passive"))
      (node (ref "V2") (pin "11") (pinfunction "SRCK_11") (pintype "input"))
    )
    (net (code "114") (name "Net-(V3C-RCK)") (class "Default")
      (node (ref "JP1") (pin "3") (pinfunction "3_3") (pintype "passive"))
      (node (ref "V3") (pin "12") (pinfunction "RCK_12") (pintype "input"))
    )
    (net (code "115") (name "Net-(V3C-SER)") (class "Default")
      (node (ref "JP1") (pin "1") (pinfunction "1_1") (pintype "passive"))
      (node (ref "V3") (pin "14") (pinfunction "SER_14") (pintype "input"))
    )
    (net (code "116") (name "Net-(V3C-SRCK)") (class "Default")
      (node (ref "JP1") (pin "2") (pinfunction "2_2") (pintype "passive"))
      (node (ref "V3") (pin "11") (pinfunction "SRCK_11") (pintype "input"))
    )
    (net (code "117") (name "Net-(X1A-KL)") (class "Default")
      (node (ref "R1") (pin "2") (pinfunction "2_2") (pintype "passive"))
      (node (ref "R2") (pin "2") (pinfunction "2_2") (pintype "passive"))
      (node (ref "R3") (pin "2") (pinfunction "2_2") (pintype "passive"))
      (node (ref "R4") (pin "2") (pinfunction "2_2") (pintype "passive"))
      (node (ref "R5") (pin "2") (pinfunction "2_2") (pintype "passive"))
      (node (ref "R6") (pin "2") (pinfunction "2_2") (pintype "passive"))
      (node (ref "R7") (pin "2") (pinfunction "2_2") (pintype "passive"))
      (node (ref "R8") (pin "2") (pinfunction "2_2") (pintype "passive"))
      (node (ref "X1") (pin "1") (pinfunction "KL_1") (pintype "passive"))
    )
    (net (code "118") (name "VCC") (class "Default")
      (node (ref "J1") (pin "1") (pinfunction "1_1") (pintype "passive"))
      (node (ref "V1") (pin "10") (pinfunction "~{SRCLR}_10") (pintype "input"))
      (node (ref "V2") (pin "10") (pinfunction "~{SRCLR}_10") (pintype "input"))
      (node (ref "V3") (pin "10") (pinfunction "~{SRCLR}_10") (pintype "input"))
    )
    (net (code "119") (name "unconnected-(IC8A-2-Pad8)") (class "Default")
      (node (ref "IC8") (pin "8") (pinfunction "2_8") (pintype "open_collector"))
    )
    (net (code "120") (name "unconnected-(IC8A-3-Pad9)") (class "Default")
      (node (ref "IC8") (pin "9") (pinfunction "3_9") (pintype "open_collector"))
    )
  )
)
